# notch_out.net
KiCad netlist of a schematic drawn in Altium Designer
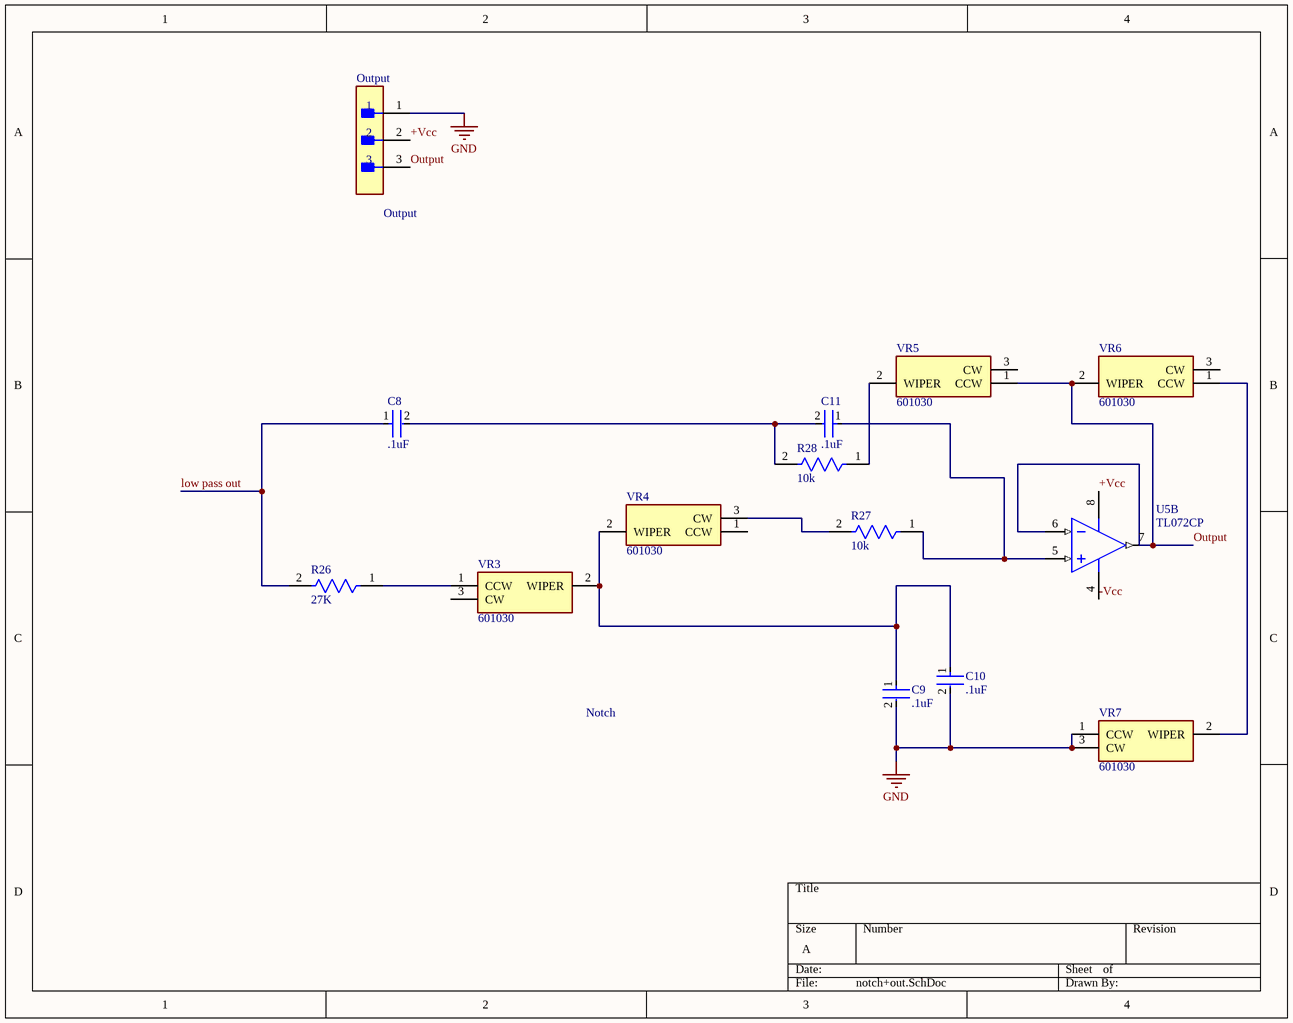
[diagram p0: notch+out.SchDoc]

(export (version "E")
  (design (tool "Eeschema 10.0.6"))
  (components
    (comp (ref "C8")
      (value ".1uF")
      (footprint "FP-K15H5-MFG")
      (description "CAP CER 0.1UF 50V X7R RADIAL")
      (fields (field (name "VOLTAGE") "50V") (field (name "TOLERANCE") "10%"))
      (libsource (lib "Altium Content Vault") (part "11868f565c42a9108669ba33697ecf6"))
    )
    (comp (ref "C9")
      (value ".1uF")
      (footprint "FP-K15H5-MFG")
      (description "CAP CER 0.1UF 50V X7R RADIAL")
      (fields (field (name "VOLTAGE") "50V") (field (name "TOLERANCE") "10%"))
      (libsource (lib "Altium Content Vault") (part "11868f565c42a9108669ba33697ecf6"))
    )
    (comp (ref "C10")
      (value ".1uF")
      (footprint "FP-K15H5-MFG")
      (description "CAP CER 0.1UF 50V X7R RADIAL")
      (fields (field (name "VOLTAGE") "50V") (field (name "TOLERANCE") "10%"))
      (libsource (lib "Altium Content Vault") (part "11868f565c42a9108669ba33697ecf6"))
    )
    (comp (ref "C11")
      (value ".1uF")
      (footprint "FP-K15H5-MFG")
      (description "CAP CER 0.1UF 50V X7R RADIAL")
      (fields (field (name "VOLTAGE") "50V") (field (name "TOLERANCE") "10%"))
      (libsource (lib "Altium Content Vault") (part "11868f565c42a9108669ba33697ecf6"))
    )
    (comp (ref "Output")
      (value "87224-3")
      (footprint "FP-87224-3-MFG")
      (description "CONN HEADER VERT 3POS 2.54MM")
      (libsource (lib "Altium Content Vault") (part "0d3f023dd272f625e17a2be33dea85f"))
    )
    (comp (ref "R26")
      (value "27K")
      (footprint "FP-CFR-25-MFG")
      (description "RES 10 OHM 1/4W 5% AXIAL")
      (fields (field (name "TOLERANCE") "5%"))
      (libsource (lib "Altium Content Vault") (part "1029c3af85768c4190bb7ad29bc67b5"))
    )
    (comp (ref "R27")
      (value "10k")
      (footprint "FP-CFR-25-MFG")
      (description "RES 10 OHM 1/4W 5% AXIAL")
      (fields (field (name "TOLERANCE") "5%"))
      (libsource (lib "Altium Content Vault") (part "1029c3af85768c4190bb7ad29bc67b5"))
    )
    (comp (ref "R28")
      (value "10k")
      (footprint "FP-CFR-25-MFG")
      (description "RES 10 OHM 1/4W 5% AXIAL")
      (fields (field (name "TOLERANCE") "5%"))
      (libsource (lib "Altium Content Vault") (part "1029c3af85768c4190bb7ad29bc67b5"))
    )
    (comp (ref "U5")
      (value "TL072CP")
      (footprint "P0008A")
      (fields (field (name "MANUFACTURER") "Texas Instruments"))
      (libsource (lib "Altium Content Vault") (part "TI-AMP-D6-2-8_D"))
    )
    (comp (ref "VR3")
      (value "601030")
      (footprint "SamacSys:601030")
      (description "Variable Resistor")
      (fields (field (name "MOUSER PART NUMBER") "581-601030"))
      (libsource (lib "") (part "601030_1"))
    )
    (comp (ref "VR4")
      (value "601030")
      (footprint "SamacSys:601030")
      (description "Variable Resistor")
      (fields (field (name "MOUSER PART NUMBER") "581-601030"))
      (libsource (lib "*") (part "601030"))
    )
    (comp (ref "VR5")
      (value "601030")
      (footprint "SamacSys:601030")
      (description "Variable Resistor")
      (fields (field (name "MOUSER PART NUMBER") "581-601030"))
      (libsource (lib "*") (part "601030"))
    )
    (comp (ref "VR6")
      (value "601030")
      (footprint "SamacSys:601030")
      (description "Variable Resistor")
      (fields (field (name "MOUSER PART NUMBER") "581-601030"))
      (libsource (lib "*") (part "601030"))
    )
    (comp (ref "VR7")
      (value "601030")
      (footprint "SamacSys:601030")
      (description "Variable Resistor")
      (fields (field (name "MOUSER PART NUMBER") "581-601030"))
      (libsource (lib "") (part "601030_1"))
    )
  )
  (nets
    (net (code "1") (name "/+Vcc") (class "Default")
      (node (ref "Output") (pin "2") (pinfunction "2_2") (pintype "passive"))
      (node (ref "U5") (pin "8") (pinfunction "VCC+_8") (pintype "power_in"))
    )
    (net (code "2") (name "/-Vcc") (class "Default")
      (node (ref "U5") (pin "4") (pinfunction "VCC-_4") (pintype "power_in"))
    )
    (net (code "3") (name "/Output") (class "Default")
      (node (ref "Output") (pin "3") (pinfunction "3_3") (pintype "passive"))
      (node (ref "U5") (pin "6") (pinfunction "IN2-_6") (pintype "input"))
      (node (ref "U5") (pin "7") (pinfunction "OUT2_7") (pintype "output"))
      (node (ref "VR5") (pin "1") (pinfunction "CCW_1") (pintype "passive"))
      (node (ref "VR6") (pin "2") (pinfunction "WIPER_2") (pintype "passive"))
    )
    (net (code "4") (name "/low pass out") (class "Default")
      (node (ref "C8") (pin "1") (pinfunction "1_1") (pintype "passive"))
      (node (ref "R26") (pin "2") (pinfunction "2_2") (pintype "passive"))
    )
    (net (code "5") (name "GND") (class "Default")
      (node (ref "C10") (pin "2") (pinfunction "2_2") (pintype "passive"))
      (node (ref "C9") (pin "2") (pinfunction "2_2") (pintype "passive"))
      (node (ref "Output") (pin "1") (pinfunction "1_1") (pintype "passive"))
      (node (ref "VR7") (pin "1") (pinfunction "CCW_1") (pintype "passive"))
      (node (ref "VR7") (pin "3") (pinfunction "CW_3") (pintype "passive"))
    )
    (net (code "6") (name "Net-(C11-Pad2)") (class "Default")
      (node (ref "C11") (pin "2") (pinfunction "2_2") (pintype "passive"))
      (node (ref "C8") (pin "2") (pinfunction "2_2") (pintype "passive"))
      (node (ref "R28") (pin "2") (pinfunction "2_2") (pintype "passive"))
    )
    (net (code "7") (name "Net-(U5B-IN2+)") (class "Default")
      (node (ref "C11") (pin "1") (pinfunction "1_1") (pintype "passive"))
      (node (ref "R27") (pin "1") (pinfunction "1_1") (pintype "passive"))
      (node (ref "U5") (pin "5") (pinfunction "IN2+_5") (pintype "input"))
    )
    (net (code "8") (name "Net-(VR3-CCW)") (class "Default")
      (node (ref "R26") (pin "1") (pinfunction "1_1") (pintype "passive"))
      (node (ref "VR3") (pin "1") (pinfunction "CCW_1") (pintype "passive"))
    )
    (net (code "9") (name "Net-(VR3-WIPER)") (class "Default")
      (node (ref "C10") (pin "1") (pinfunction "1_1") (pintype "passive"))
      (node (ref "C9") (pin "1") (pinfunction "1_1") (pintype "passive"))
      (node (ref "VR3") (pin "2") (pinfunction "WIPER_2") (pintype "passive"))
      (node (ref "VR4") (pin "2") (pinfunction "WIPER_2") (pintype "passive"))
    )
    (net (code "10") (name "Net-(VR4-CW)") (class "Default")
      (node (ref "R27") (pin "2") (pinfunction "2_2") (pintype "passive"))
      (node (ref "VR4") (pin "3") (pinfunction "CW_3") (pintype "passive"))
    )
    (net (code "11") (name "Net-(VR5-WIPER)") (class "Default")
      (node (ref "R28") (pin "1") (pinfunction "1_1") (pintype "passive"))
      (node (ref "VR5") (pin "2") (pinfunction "WIPER_2") (pintype "passive"))
    )
    (net (code "12") (name "Net-(VR6-CCW)") (class "Default")
      (node (ref "VR6") (pin "1") (pinfunction "CCW_1") (pintype "passive"))
      (node (ref "VR7") (pin "2") (pinfunction "WIPER_2") (pintype "passive"))
    )
    (net (code "13") (name "unconnected-(VR3-CW-Pad3)") (class "Default")
      (node (ref "VR3") (pin "3") (pinfunction "CW_3") (pintype "passive"))
    )
    (net (code "14") (name "unconnected-(VR4-CCW-Pad1)") (class "Default")
      (node (ref "VR4") (pin "1") (pinfunction "CCW_1") (pintype "passive"))
    )
    (net (code "15") (name "unconnected-(VR5-CW-Pad3)") (class "Default")
      (node (ref "VR5") (pin "3") (pinfunction "CW_3") (pintype "passive"))
    )
    (net (code "16") (name "unconnected-(VR6-CW-Pad3)") (class "Default")
      (node (ref "VR6") (pin "3") (pinfunction "CW_3") (pintype "passive"))
    )
  )
)
